# Buck_Sense1.net
KiCad netlist of a schematic drawn in Altium Designer
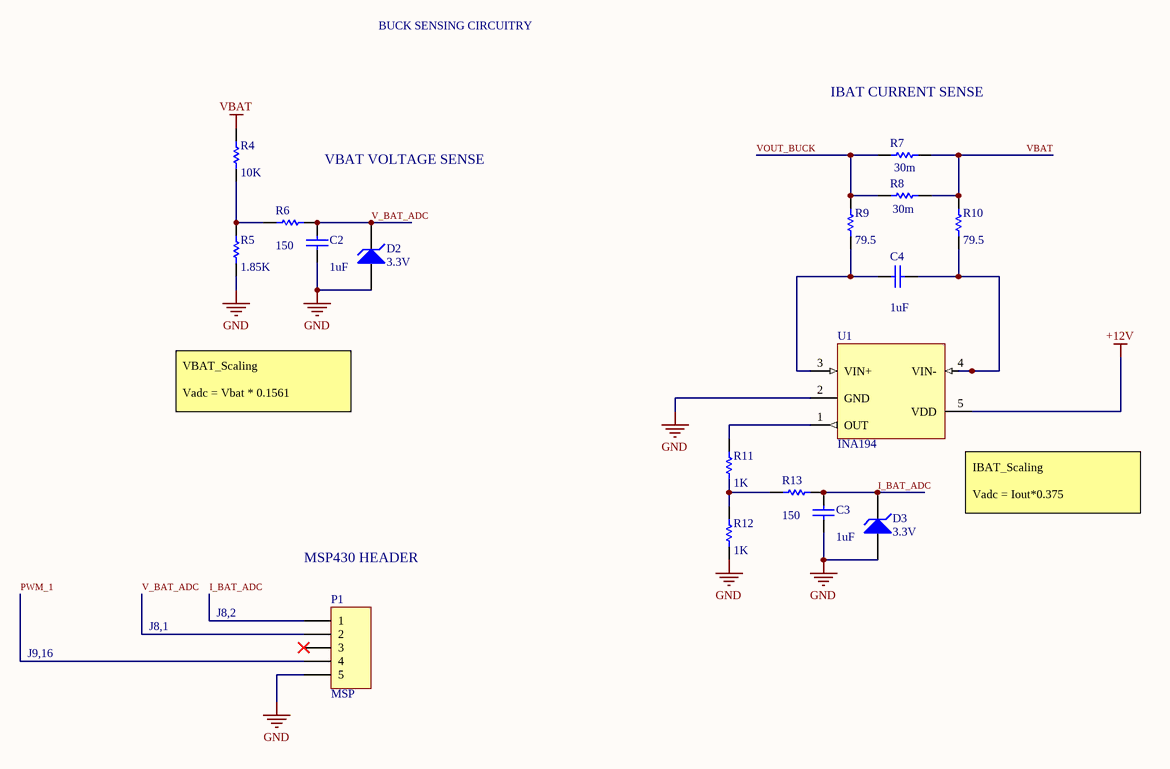
[diagram p0: Buck_Sense1.SchDoc]

(export (version "E")
  (design (tool "Eeschema 10.0.6"))
  (components
    (comp (ref "C2")
      (value "1uF")
      (footprint "RAD-0.3")
      (description "Capacitor")
      (fields (field (name "PUBLISHER") "Altium Limited"))
      (libsource (lib "Miscellaneous Devices") (part "Cap"))
    )
    (comp (ref "C3")
      (value "1uF")
      (footprint "RAD-0.3")
      (description "Capacitor")
      (fields (field (name "PUBLISHER") "Altium Limited"))
      (libsource (lib "Miscellaneous Devices") (part "Cap"))
    )
    (comp (ref "C4")
      (value "1uF")
      (footprint "RAD-0.3")
      (description "Capacitor")
      (fields (field (name "PUBLISHER") "Altium Limited"))
      (libsource (lib "Miscellaneous Devices") (part "Cap"))
    )
    (comp (ref "D2")
      (value "3.3V")
      (footprint "DIODE-0.7")
      (description "Zener Diode")
      (fields (field (name "PUBLISHER") "Altium Limited"))
      (libsource (lib "Miscellaneous Devices") (part "D Zener"))
    )
    (comp (ref "D3")
      (value "3.3V")
      (footprint "DIODE-0.7")
      (description "Zener Diode")
      (fields (field (name "PUBLISHER") "Altium Limited"))
      (libsource (lib "Miscellaneous Devices") (part "D Zener"))
    )
    (comp (ref "P1")
      (value "MSP")
      (footprint "HDR1X5")
      (description "Header, 5-Pin")
      (fields (field (name "PUBLISHER") "Altium Limited"))
      (libsource (lib "Miscellaneous Connectors") (part "Header 5"))
    )
    (comp (ref "R4")
      (value "10K")
      (footprint "AXIAL-0.3")
      (description "Resistor")
      (fields (field (name "PUBLISHER") "Altium Limited"))
      (libsource (lib "Miscellaneous Devices") (part "Res1"))
    )
    (comp (ref "R5")
      (value "1.85K")
      (footprint "AXIAL-0.3")
      (description "Resistor")
      (fields (field (name "PUBLISHER") "Altium Limited"))
      (libsource (lib "Miscellaneous Devices") (part "Res1"))
    )
    (comp (ref "R6")
      (value "150")
      (footprint "AXIAL-0.3")
      (description "Resistor")
      (fields (field (name "PUBLISHER") "Altium Limited"))
      (libsource (lib "Miscellaneous Devices") (part "Res1"))
    )
    (comp (ref "R7")
      (value "30m")
      (footprint "AXIAL-0.3")
      (description "Resistor")
      (fields (field (name "PUBLISHER") "Altium Limited"))
      (libsource (lib "Miscellaneous Devices") (part "Res1"))
    )
    (comp (ref "R8")
      (value "30m")
      (footprint "AXIAL-0.3")
      (description "Resistor")
      (fields (field (name "PUBLISHER") "Altium Limited"))
      (libsource (lib "Miscellaneous Devices") (part "Res1"))
    )
    (comp (ref "R9")
      (value "79.5")
      (footprint "AXIAL-0.3")
      (description "Resistor")
      (fields (field (name "PUBLISHER") "Altium Limited"))
      (libsource (lib "Miscellaneous Devices") (part "Res1"))
    )
    (comp (ref "R10")
      (value "79.5")
      (footprint "AXIAL-0.3")
      (description "Resistor")
      (fields (field (name "PUBLISHER") "Altium Limited"))
      (libsource (lib "Miscellaneous Devices") (part "Res1"))
    )
    (comp (ref "R11")
      (value "1K")
      (footprint "AXIAL-0.3")
      (description "Resistor")
      (fields (field (name "PUBLISHER") "Altium Limited"))
      (libsource (lib "Miscellaneous Devices") (part "Res1"))
    )
    (comp (ref "R12")
      (value "1K")
      (footprint "AXIAL-0.3")
      (description "Resistor")
      (fields (field (name "PUBLISHER") "Altium Limited"))
      (libsource (lib "Miscellaneous Devices") (part "Res1"))
    )
    (comp (ref "R13")
      (value "150")
      (footprint "AXIAL-0.3")
      (description "Resistor")
      (fields (field (name "PUBLISHER") "Altium Limited"))
      (libsource (lib "Miscellaneous Devices") (part "Res1"))
    )
    (comp (ref "U1")
      (value "INA194")
      (description "CURRENT SHUNT MONITOR")
      (libsource (lib "*") (part "INA194"))
    )
  )
  (nets
    (net (code "1") (name "+12V") (class "Default")
      (node (ref "U1") (pin "5") (pinfunction "VDD_5") (pintype "power_in"))
    )
    (net (code "2") (name "/I_BAT_ADC") (class "Default")
      (node (ref "C3") (pin "2") (pinfunction "2_2") (pintype "passive"))
      (node (ref "D3") (pin "2") (pinfunction "K_2") (pintype "passive"))
      (node (ref "P1") (pin "1") (pinfunction "1_1") (pintype "passive"))
      (node (ref "R13") (pin "2") (pinfunction "2_2") (pintype "passive"))
    )
    (net (code "3") (name "/PWM_1") (class "Default")
      (node (ref "P1") (pin "4") (pinfunction "4_4") (pintype "passive"))
    )
    (net (code "4") (name "/VOUT_BUCK") (class "Default")
      (node (ref "R7") (pin "2") (pinfunction "2_2") (pintype "passive"))
      (node (ref "R8") (pin "2") (pinfunction "2_2") (pintype "passive"))
      (node (ref "R9") (pin "1") (pinfunction "1_1") (pintype "passive"))
    )
    (net (code "5") (name "/V_BAT_ADC") (class "Default")
      (node (ref "C2") (pin "2") (pinfunction "2_2") (pintype "passive"))
      (node (ref "D2") (pin "2") (pinfunction "K_2") (pintype "passive"))
      (node (ref "P1") (pin "2") (pinfunction "2_2") (pintype "passive"))
      (node (ref "R6") (pin "1") (pinfunction "1_1") (pintype "passive"))
    )
    (net (code "6") (name "GND") (class "Default")
      (node (ref "C2") (pin "1") (pinfunction "1_1") (pintype "passive"))
      (node (ref "C3") (pin "1") (pinfunction "1_1") (pintype "passive"))
      (node (ref "D2") (pin "1") (pinfunction "A_1") (pintype "passive"))
      (node (ref "D3") (pin "1") (pinfunction "A_1") (pintype "passive"))
      (node (ref "P1") (pin "5") (pinfunction "5_5") (pintype "passive"))
      (node (ref "R12") (pin "2") (pinfunction "2_2") (pintype "passive"))
      (node (ref "R5") (pin "1") (pinfunction "1_1") (pintype "passive"))
      (node (ref "U1") (pin "2") (pinfunction "GND_2") (pintype "power_in"))
    )
    (net (code "7") (name "Net-(R4-Pad1)") (class "Default")
      (node (ref "R4") (pin "1") (pinfunction "1_1") (pintype "passive"))
      (node (ref "R5") (pin "2") (pinfunction "2_2") (pintype "passive"))
      (node (ref "R6") (pin "2") (pinfunction "2_2") (pintype "passive"))
    )
    (net (code "8") (name "Net-(R11-Pad2)") (class "Default")
      (node (ref "R11") (pin "2") (pinfunction "2_2") (pintype "passive"))
      (node (ref "R12") (pin "1") (pinfunction "1_1") (pintype "passive"))
      (node (ref "R13") (pin "1") (pinfunction "1_1") (pintype "passive"))
    )
    (net (code "9") (name "Net-(U1-OUT)") (class "Default")
      (node (ref "R11") (pin "1") (pinfunction "1_1") (pintype "passive"))
      (node (ref "U1") (pin "1") (pinfunction "OUT_1") (pintype "output"))
    )
    (net (code "10") (name "Net-(U1-VIN+)") (class "Default")
      (node (ref "C4") (pin "2") (pinfunction "2_2") (pintype "passive"))
      (node (ref "R9") (pin "2") (pinfunction "2_2") (pintype "passive"))
      (node (ref "U1") (pin "3") (pinfunction "VIN+_3") (pintype "input"))
    )
    (net (code "11") (name "Net-(U1-VIN-)") (class "Default")
      (node (ref "C4") (pin "1") (pinfunction "1_1") (pintype "passive"))
      (node (ref "R10") (pin "2") (pinfunction "2_2") (pintype "passive"))
      (node (ref "U1") (pin "4") (pinfunction "VIN-_4") (pintype "input"))
    )
    (net (code "12") (name "VBAT") (class "Default")
      (node (ref "R10") (pin "1") (pinfunction "1_1") (pintype "passive"))
      (node (ref "R4") (pin "2") (pinfunction "2_2") (pintype "passive"))
      (node (ref "R7") (pin "1") (pinfunction "1_1") (pintype "passive"))
      (node (ref "R8") (pin "1") (pinfunction "1_1") (pintype "passive"))
    )
    (net (code "13") (name "unconnected-(P1-Pad3)") (class "Default")
      (node (ref "P1") (pin "3") (pinfunction "3_3") (pintype "passive+no_connect"))
    )
  )
)
